# APC1_OBC.net
KiCad netlist of a schematic drawn in Altium Designer
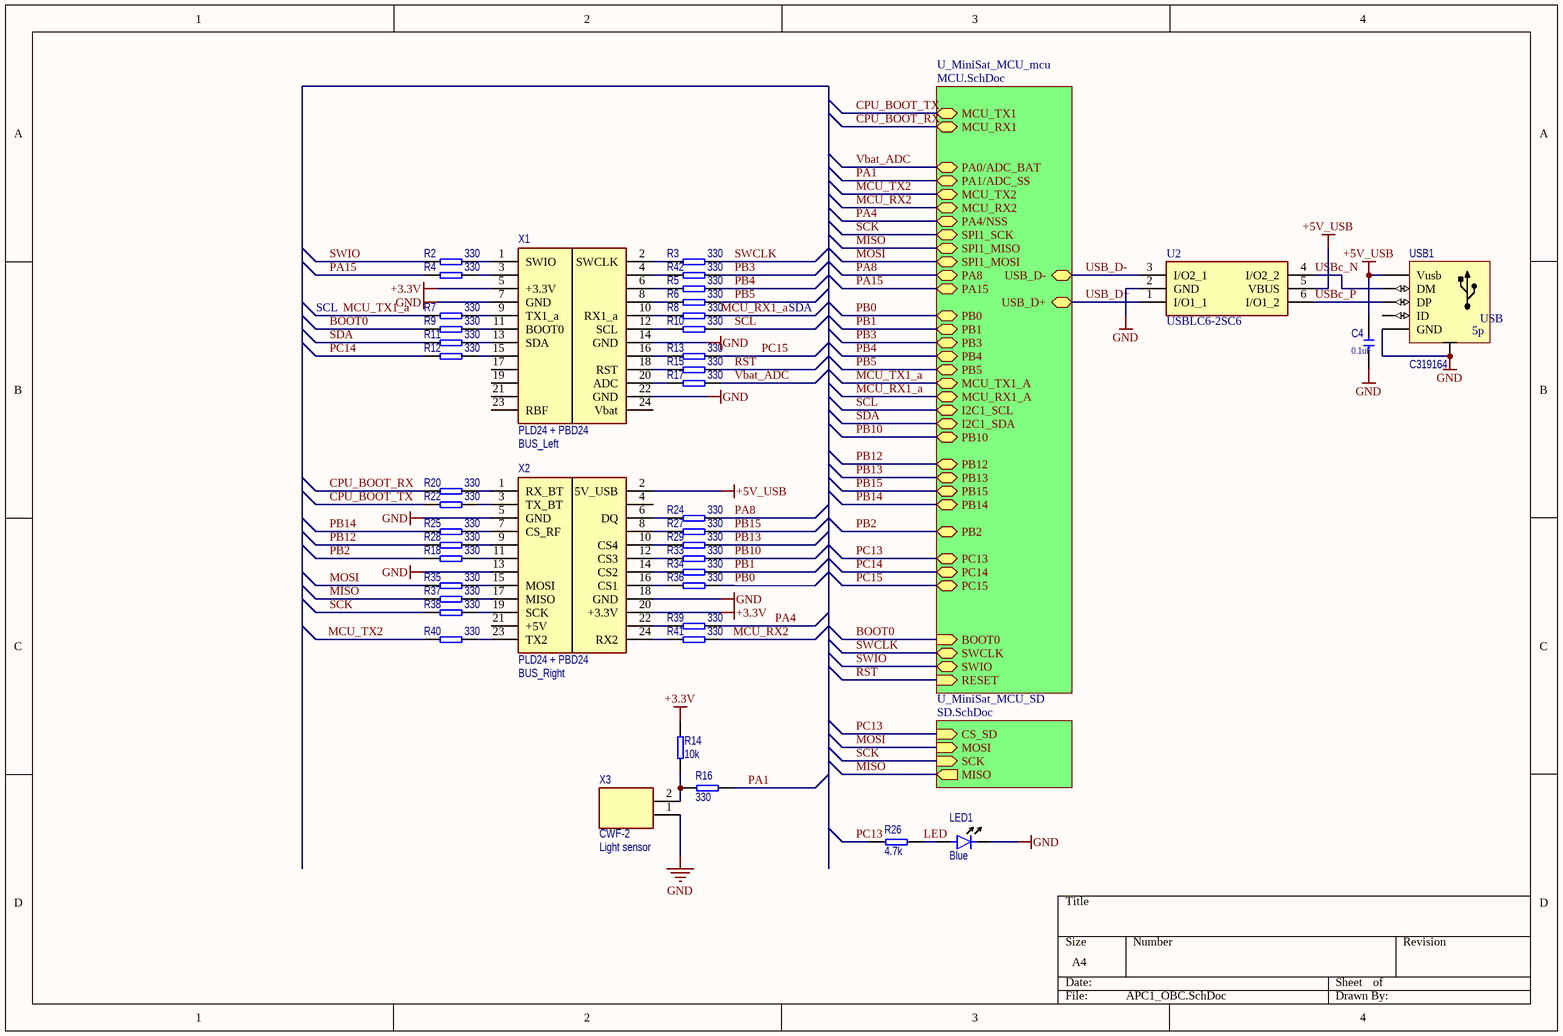
[diagram p0: APC1_OBC.SchDoc]

(export (version "E")
  (design (tool "Eeschema 10.0.6"))
  (components
    (comp (ref "C4")
      (value "0.1uF")
      (footprint "CERCAP 0402")
      (description "Capacitor")
      (fields (field (name "Comment") "CERCAP 0402 0.1uF * X7R"))
      (libsource (lib "!main") (part "!Capacitor"))
    )
    (comp (ref "LED1")
      (value "Blue")
      (footprint "LED 0603")
      (description "Light Emittering Diode")
      (fields (field (name "Comment") "LED 0603 Blue"))
      (libsource (lib "!main") (part "LED"))
    )
    (comp (ref "R2")
      (value "330")
      (footprint "RES 0402")
      (description "Resistor")
      (fields (field (name "Comment") "RES 0402 330"))
      (libsource (lib "!main") (part "!Resistor"))
    )
    (comp (ref "R3")
      (value "330")
      (footprint "RES 0402")
      (description "Resistor")
      (fields (field (name "Comment") "RES 0402 330"))
      (libsource (lib "!main") (part "!Resistor"))
    )
    (comp (ref "R4")
      (value "330")
      (footprint "RES 0402")
      (description "Resistor")
      (fields (field (name "Comment") "RES 0402 330"))
      (libsource (lib "!main") (part "!Resistor"))
    )
    (comp (ref "R5")
      (value "330")
      (footprint "RES 0402")
      (description "Resistor")
      (fields (field (name "Comment") "RES 0402 330"))
      (libsource (lib "!main") (part "!Resistor"))
    )
    (comp (ref "R6")
      (value "330")
      (footprint "RES 0402")
      (description "Resistor")
      (fields (field (name "Comment") "RES 0402 330"))
      (libsource (lib "!main") (part "!Resistor"))
    )
    (comp (ref "R7")
      (value "330")
      (footprint "RES 0402")
      (description "Resistor")
      (fields (field (name "Comment") "RES 0402 330"))
      (libsource (lib "!main") (part "!Resistor"))
    )
    (comp (ref "R8")
      (value "330")
      (footprint "RES 0402")
      (description "Resistor")
      (fields (field (name "Comment") "RES 0402 330"))
      (libsource (lib "!main") (part "!Resistor"))
    )
    (comp (ref "R9")
      (value "330")
      (footprint "RES 0402")
      (description "Resistor")
      (fields (field (name "Comment") "RES 0402 330"))
      (libsource (lib "!main") (part "!Resistor"))
    )
    (comp (ref "R10")
      (value "330")
      (footprint "RES 0402")
      (description "Resistor")
      (fields (field (name "Comment") "RES 0402 330"))
      (libsource (lib "!main") (part "!Resistor"))
    )
    (comp (ref "R11")
      (value "330")
      (footprint "RES 0402")
      (description "Resistor")
      (fields (field (name "Comment") "RES 0402 330"))
      (libsource (lib "!main") (part "!Resistor"))
    )
    (comp (ref "R12")
      (value "330")
      (footprint "RES 0402")
      (description "Resistor")
      (fields (field (name "Comment") "RES 0402 330"))
      (libsource (lib "!main") (part "!Resistor"))
    )
    (comp (ref "R13")
      (value "330")
      (footprint "RES 0402")
      (description "Resistor")
      (fields (field (name "Comment") "RES 0402 330"))
      (libsource (lib "!main") (part "!Resistor"))
    )
    (comp (ref "R14")
      (value "10k")
      (footprint "RES 0402")
      (description "Resistor")
      (fields (field (name "Comment") "RES 0402 10k"))
      (libsource (lib "!main") (part "!Resistor"))
    )
    (comp (ref "R15")
      (value "330")
      (footprint "RES 0402")
      (description "Resistor")
      (fields (field (name "Comment") "RES 0402 330"))
      (libsource (lib "!main") (part "!Resistor"))
    )
    (comp (ref "R16")
      (value "330")
      (footprint "RES 0603")
      (description "Resistor")
      (fields (field (name "Comment") "RES 0603 330"))
      (libsource (lib "!main") (part "!Resistor"))
    )
    (comp (ref "R17")
      (value "330")
      (footprint "RES 0402")
      (description "Resistor")
      (fields (field (name "Comment") "RES 0402 330"))
      (libsource (lib "!main") (part "!Resistor"))
    )
    (comp (ref "R18")
      (value "330")
      (footprint "RES 0402")
      (description "Resistor")
      (fields (field (name "Comment") "RES 0402 330"))
      (libsource (lib "!main") (part "!Resistor"))
    )
    (comp (ref "R20")
      (value "330")
      (footprint "RES 0402")
      (description "Resistor")
      (fields (field (name "Comment") "RES 0402 330"))
      (libsource (lib "!main") (part "!Resistor"))
    )
    (comp (ref "R22")
      (value "330")
      (footprint "RES 0402")
      (description "Resistor")
      (fields (field (name "Comment") "RES 0402 330"))
      (libsource (lib "!main") (part "!Resistor"))
    )
    (comp (ref "R24")
      (value "330")
      (footprint "RES 0402")
      (description "Resistor")
      (fields (field (name "Comment") "RES 0402 330"))
      (libsource (lib "!main") (part "!Resistor"))
    )
    (comp (ref "R25")
      (value "330")
      (footprint "RES 0402")
      (description "Resistor")
      (fields (field (name "Comment") "RES 0402 330"))
      (libsource (lib "!main") (part "!Resistor"))
    )
    (comp (ref "R26")
      (value "4.7k")
      (footprint "RES 0402")
      (description "Resistor")
      (fields (field (name "Comment") "RES 0402 4.7k"))
      (libsource (lib "!main") (part "!Resistor"))
    )
    (comp (ref "R27")
      (value "330")
      (footprint "RES 0402")
      (description "Resistor")
      (fields (field (name "Comment") "RES 0402 330"))
      (libsource (lib "!main") (part "!Resistor"))
    )
    (comp (ref "R28")
      (value "330")
      (footprint "RES 0402")
      (description "Resistor")
      (fields (field (name "Comment") "RES 0402 330"))
      (libsource (lib "!main") (part "!Resistor"))
    )
    (comp (ref "R29")
      (value "330")
      (footprint "RES 0402")
      (description "Resistor")
      (fields (field (name "Comment") "RES 0402 330"))
      (libsource (lib "!main") (part "!Resistor"))
    )
    (comp (ref "R33")
      (value "330")
      (footprint "RES 0402")
      (description "Resistor")
      (fields (field (name "Comment") "RES 0402 330"))
      (libsource (lib "!main") (part "!Resistor"))
    )
    (comp (ref "R34")
      (value "330")
      (footprint "RES 0402")
      (description "Resistor")
      (fields (field (name "Comment") "RES 0402 330"))
      (libsource (lib "!main") (part "!Resistor"))
    )
    (comp (ref "R35")
      (value "330")
      (footprint "RES 0402")
      (description "Resistor")
      (fields (field (name "Comment") "RES 0402 330"))
      (libsource (lib "!main") (part "!Resistor"))
    )
    (comp (ref "R36")
      (value "330")
      (footprint "RES 0402")
      (description "Resistor")
      (fields (field (name "Comment") "RES 0402 330"))
      (libsource (lib "!main") (part "!Resistor"))
    )
    (comp (ref "R37")
      (value "330")
      (footprint "RES 0402")
      (description "Resistor")
      (fields (field (name "Comment") "RES 0402 330"))
      (libsource (lib "!main") (part "!Resistor"))
    )
    (comp (ref "R38")
      (value "330")
      (footprint "RES 0402")
      (description "Resistor")
      (fields (field (name "Comment") "RES 0402 330"))
      (libsource (lib "!main") (part "!Resistor"))
    )
    (comp (ref "R39")
      (value "330")
      (footprint "RES 0402")
      (description "Resistor")
      (fields (field (name "Comment") "RES 0402 330"))
      (libsource (lib "!main") (part "!Resistor"))
    )
    (comp (ref "R40")
      (value "330")
      (footprint "RES 0402")
      (description "Resistor")
      (fields (field (name "Comment") "RES 0402 330"))
      (libsource (lib "!main") (part "!Resistor"))
    )
    (comp (ref "R41")
      (value "330")
      (footprint "RES 0402")
      (description "Resistor")
      (fields (field (name "Comment") "RES 0402 330"))
      (libsource (lib "!main") (part "!Resistor"))
    )
    (comp (ref "R42")
      (value "330")
      (footprint "RES 0402")
      (description "Resistor")
      (fields (field (name "Comment") "RES 0402 330"))
      (libsource (lib "!main") (part "!Resistor"))
    )
    (comp (ref "U2")
      (value "USBLC6-2SC6")
      (footprint "SOT-666")
      (description "Integrated Circuit")
      (fields (field (name "LCSC PART #") "C7519"))
      (libsource (lib "*") (part "USBLC6-2SC6"))
    )
    (comp (ref "USB1")
      (value "C319164")
      (footprint "USB-Micro_TH")
      (description "USB 5-pin")
      (libsource (lib "connectors") (part "USB(5p)"))
    )
    (comp (ref "X1")
      (value "PLD24 + PBD24")
      (footprint "PICOSAT_CNN")
      (description "10x2 header")
      (fields (field (name "PURPOSE") "BUS_Left"))
      (libsource (lib "connectors") (part "Header 2x12"))
    )
    (comp (ref "X2")
      (value "PLD24 + PBD24")
      (footprint "PICOSAT_CNN")
      (description "10x2 header")
      (fields (field (name "PURPOSE") "BUS_Right"))
      (libsource (lib "connectors") (part "Header 2x12"))
    )
    (comp (ref "X3")
      (value "CWF-2")
      (footprint "PBS-2-2.54")
      (description "2x1 header")
      (fields (field (name "PURPOSE") "Light sensor"))
      (libsource (lib "connectors") (part "Header 1x2"))
    )
  )
  (nets
    (net (code "1") (name "+3.3V") (class "Default")
      (node (ref "R14") (pin "2") (pinfunction "12_2") (pintype "passive"))
      (node (ref "X1") (pin "5") (pinfunction "+3.3V_5") (pintype "passive"))
      (node (ref "X2") (pin "20") (pinfunction "ADC_20") (pintype "passive"))
    )
    (net (code "2") (name "+5V_USB") (class "Default")
      (node (ref "C4") (pin "2") (pintype "passive"))
      (node (ref "U2") (pin "5") (pinfunction "VBUS_5") (pintype "passive"))
      (node (ref "USB1") (pin "Vusb") (pinfunction "Vusb_Vusb") (pintype "power_in"))
      (node (ref "X2") (pin "2") (pinfunction "SWCLK_2") (pintype "passive"))
    )
    (net (code "3") (name "/BOOT0") (class "Default")
      (node (ref "R9") (pin "1") (pinfunction "11_1") (pintype "passive"))
    )
    (net (code "4") (name "/CPU_BOOT_RX") (class "Default")
      (node (ref "R20") (pin "1") (pinfunction "11_1") (pintype "passive"))
    )
    (net (code "5") (name "/CPU_BOOT_TX") (class "Default")
      (node (ref "R22") (pin "1") (pinfunction "11_1") (pintype "passive"))
    )
    (net (code "6") (name "/LED") (class "Default")
      (node (ref "LED1") (pin "1") (pinfunction "Anode_1") (pintype "passive"))
      (node (ref "R26") (pin "2") (pinfunction "12_2") (pintype "passive"))
    )
    (net (code "7") (name "/MCU_RX1_a") (class "Default")
      (node (ref "R8") (pin "2") (pinfunction "12_2") (pintype "passive"))
    )
    (net (code "8") (name "/MCU_RX2") (class "Default")
      (node (ref "R41") (pin "2") (pinfunction "12_2") (pintype "passive"))
    )
    (net (code "9") (name "/MCU_TX1_a") (class "Default")
      (node (ref "R7") (pin "1") (pinfunction "11_1") (pintype "passive"))
    )
    (net (code "10") (name "/MCU_TX2") (class "Default")
      (node (ref "R40") (pin "1") (pinfunction "11_1") (pintype "passive"))
    )
    (net (code "11") (name "/MISO") (class "Default")
      (node (ref "R37") (pin "1") (pinfunction "11_1") (pintype "passive"))
    )
    (net (code "12") (name "/MOSI") (class "Default")
      (node (ref "R35") (pin "1") (pinfunction "11_1") (pintype "passive"))
    )
    (net (code "13") (name "/PA1") (class "Default")
      (node (ref "R16") (pin "1") (pinfunction "11_1") (pintype "passive"))
    )
    (net (code "14") (name "/PA4") (class "Default")
      (node (ref "R39") (pin "2") (pinfunction "12_2") (pintype "passive"))
    )
    (net (code "15") (name "/PA8") (class "Default")
      (node (ref "R24") (pin "2") (pinfunction "12_2") (pintype "passive"))
    )
    (net (code "16") (name "/PA15") (class "Default")
      (node (ref "R4") (pin "1") (pinfunction "11_1") (pintype "passive"))
    )
    (net (code "17") (name "/PB0") (class "Default")
      (node (ref "R36") (pin "2") (pinfunction "12_2") (pintype "passive"))
    )
    (net (code "18") (name "/PB1") (class "Default")
      (node (ref "R34") (pin "2") (pinfunction "12_2") (pintype "passive"))
    )
    (net (code "19") (name "/PB2") (class "Default")
      (node (ref "R18") (pin "1") (pinfunction "11_1") (pintype "passive"))
    )
    (net (code "20") (name "/PB3") (class "Default")
      (node (ref "R42") (pin "2") (pinfunction "12_2") (pintype "passive"))
    )
    (net (code "21") (name "/PB4") (class "Default")
      (node (ref "R5") (pin "2") (pinfunction "12_2") (pintype "passive"))
    )
    (net (code "22") (name "/PB5") (class "Default")
      (node (ref "R6") (pin "2") (pinfunction "12_2") (pintype "passive"))
    )
    (net (code "23") (name "/PB10") (class "Default")
      (node (ref "R33") (pin "2") (pinfunction "12_2") (pintype "passive"))
    )
    (net (code "24") (name "/PB12") (class "Default")
      (node (ref "R28") (pin "1") (pinfunction "11_1") (pintype "passive"))
    )
    (net (code "25") (name "/PB13") (class "Default")
      (node (ref "R29") (pin "2") (pinfunction "12_2") (pintype "passive"))
    )
    (net (code "26") (name "/PB14") (class "Default")
      (node (ref "R25") (pin "1") (pinfunction "11_1") (pintype "passive"))
    )
    (net (code "27") (name "/PB15") (class "Default")
      (node (ref "R27") (pin "2") (pinfunction "12_2") (pintype "passive"))
    )
    (net (code "28") (name "/PC13") (class "Default")
      (node (ref "R26") (pin "1") (pinfunction "11_1") (pintype "passive"))
    )
    (net (code "29") (name "/PC14") (class "Default")
      (node (ref "R12") (pin "1") (pinfunction "11_1") (pintype "passive"))
    )
    (net (code "30") (name "/PC15") (class "Default")
      (node (ref "R13") (pin "2") (pinfunction "12_2") (pintype "passive"))
    )
    (net (code "31") (name "/RST") (class "Default")
      (node (ref "R15") (pin "2") (pinfunction "12_2") (pintype "passive"))
    )
    (net (code "32") (name "/SCK") (class "Default")
      (node (ref "R38") (pin "1") (pinfunction "11_1") (pintype "passive"))
    )
    (net (code "33") (name "/SCL") (class "Default")
      (node (ref "R10") (pin "2") (pinfunction "12_2") (pintype "passive"))
    )
    (net (code "34") (name "/SDA") (class "Default")
      (node (ref "R11") (pin "1") (pinfunction "11_1") (pintype "passive"))
    )
    (net (code "35") (name "/SWCLK") (class "Default")
      (node (ref "R3") (pin "2") (pinfunction "12_2") (pintype "passive"))
    )
    (net (code "36") (name "/SWIO") (class "Default")
      (node (ref "R2") (pin "1") (pinfunction "11_1") (pintype "passive"))
    )
    (net (code "37") (name "/USB_D+") (class "Default")
      (node (ref "U2") (pin "1") (pinfunction "I/O1_1_1") (pintype "passive"))
    )
    (net (code "38") (name "/USB_D-") (class "Default")
      (node (ref "U2") (pin "3") (pinfunction "I/O2_1_3") (pintype "passive"))
    )
    (net (code "39") (name "/USBc_N") (class "Default")
      (node (ref "U2") (pin "4") (pinfunction "I/O2_2_4") (pintype "passive"))
      (node (ref "USB1") (pin "DM") (pinfunction "DM_DM") (pintype "bidirectional"))
    )
    (net (code "40") (name "/USBc_P") (class "Default")
      (node (ref "U2") (pin "6") (pinfunction "I/O1_2_6") (pintype "passive"))
      (node (ref "USB1") (pin "DP") (pinfunction "DP_DP") (pintype "bidirectional"))
    )
    (net (code "41") (name "/Vbat_ADC") (class "Default")
      (node (ref "R17") (pin "2") (pinfunction "12_2") (pintype "passive"))
    )
    (net (code "42") (name "GND") (class "Default")
      (node (ref "C4") (pin "1") (pintype "passive"))
      (node (ref "LED1") (pin "2") (pinfunction "Cathode_2") (pintype "passive"))
      (node (ref "U2") (pin "2") (pinfunction "GND_2") (pintype "passive"))
      (node (ref "USB1") (pin "GND") (pinfunction "GND_GND") (pintype "power_in"))
      (node (ref "USB1") (pin "TH") (pinfunction "TH_TH") (pintype "power_in"))
      (node (ref "X1") (pin "14") (pinfunction "GND_14") (pintype "passive"))
      (node (ref "X1") (pin "22") (pinfunction "GND_22") (pintype "passive"))
      (node (ref "X1") (pin "7") (pinfunction "GND_7") (pintype "passive"))
      (node (ref "X2") (pin "13") (pinfunction "SDA_13") (pintype "passive"))
      (node (ref "X2") (pin "18") (pinfunction "RST_18") (pintype "passive"))
      (node (ref "X2") (pin "5") (pinfunction "+3.3V_5") (pintype "passive"))
      (node (ref "X3") (pin "1") (pinfunction "1_1") (pintype "passive"))
    )
    (net (code "43") (name "Net-(R2-12)") (class "Default")
      (node (ref "R2") (pin "2") (pinfunction "12_2") (pintype "passive"))
      (node (ref "X1") (pin "1") (pinfunction "SWIO_1") (pintype "passive"))
    )
    (net (code "44") (name "Net-(R3-11)") (class "Default")
      (node (ref "R3") (pin "1") (pinfunction "11_1") (pintype "passive"))
      (node (ref "X1") (pin "2") (pinfunction "SWCLK_2") (pintype "passive"))
    )
    (net (code "45") (name "Net-(R4-12)") (class "Default")
      (node (ref "R4") (pin "2") (pinfunction "12_2") (pintype "passive"))
      (node (ref "X1") (pin "3") (pintype "passive"))
    )
    (net (code "46") (name "Net-(R5-11)") (class "Default")
      (node (ref "R5") (pin "1") (pinfunction "11_1") (pintype "passive"))
      (node (ref "X1") (pin "6") (pintype "passive"))
    )
    (net (code "47") (name "Net-(R6-11)") (class "Default")
      (node (ref "R6") (pin "1") (pinfunction "11_1") (pintype "passive"))
      (node (ref "X1") (pin "8") (pintype "passive"))
    )
    (net (code "48") (name "Net-(R7-12)") (class "Default")
      (node (ref "R7") (pin "2") (pinfunction "12_2") (pintype "passive"))
      (node (ref "X1") (pin "9") (pinfunction "TX1_a_9") (pintype "passive"))
    )
    (net (code "49") (name "Net-(R8-11)") (class "Default")
      (node (ref "R8") (pin "1") (pinfunction "11_1") (pintype "passive"))
      (node (ref "X1") (pin "10") (pinfunction "RX1_a_10") (pintype "passive"))
    )
    (net (code "50") (name "Net-(R9-12)") (class "Default")
      (node (ref "R9") (pin "2") (pinfunction "12_2") (pintype "passive"))
      (node (ref "X1") (pin "11") (pinfunction "BOOT0_11") (pintype "passive"))
    )
    (net (code "51") (name "Net-(R10-11)") (class "Default")
      (node (ref "R10") (pin "1") (pinfunction "11_1") (pintype "passive"))
      (node (ref "X1") (pin "12") (pinfunction "SCL_12") (pintype "passive"))
    )
    (net (code "52") (name "Net-(R11-12)") (class "Default")
      (node (ref "R11") (pin "2") (pinfunction "12_2") (pintype "passive"))
      (node (ref "X1") (pin "13") (pinfunction "SDA_13") (pintype "passive"))
    )
    (net (code "53") (name "Net-(R12-12)") (class "Default")
      (node (ref "R12") (pin "2") (pinfunction "12_2") (pintype "passive"))
      (node (ref "X1") (pin "15") (pintype "passive"))
    )
    (net (code "54") (name "Net-(R13-11)") (class "Default")
      (node (ref "R13") (pin "1") (pinfunction "11_1") (pintype "passive"))
      (node (ref "X1") (pin "16") (pintype "passive"))
    )
    (net (code "55") (name "Net-(R14-11)") (class "Default")
      (node (ref "R14") (pin "1") (pinfunction "11_1") (pintype "passive"))
      (node (ref "R16") (pin "2") (pinfunction "12_2") (pintype "passive"))
      (node (ref "X3") (pin "2") (pinfunction "2_2") (pintype "passive"))
    )
    (net (code "56") (name "Net-(R15-11)") (class "Default")
      (node (ref "R15") (pin "1") (pinfunction "11_1") (pintype "passive"))
      (node (ref "X1") (pin "18") (pinfunction "RST_18") (pintype "passive"))
    )
    (net (code "57") (name "Net-(R17-11)") (class "Default")
      (node (ref "R17") (pin "1") (pinfunction "11_1") (pintype "passive"))
      (node (ref "X1") (pin "20") (pinfunction "ADC_20") (pintype "passive"))
    )
    (net (code "58") (name "Net-(R18-12)") (class "Default")
      (node (ref "R18") (pin "2") (pinfunction "12_2") (pintype "passive"))
      (node (ref "X2") (pin "11") (pinfunction "BOOT0_11") (pintype "passive"))
    )
    (net (code "59") (name "Net-(R20-12)") (class "Default")
      (node (ref "R20") (pin "2") (pinfunction "12_2") (pintype "passive"))
      (node (ref "X2") (pin "1") (pinfunction "SWIO_1") (pintype "passive"))
    )
    (net (code "60") (name "Net-(R22-12)") (class "Default")
      (node (ref "R22") (pin "2") (pinfunction "12_2") (pintype "passive"))
      (node (ref "X2") (pin "3") (pintype "passive"))
    )
    (net (code "61") (name "Net-(R24-11)") (class "Default")
      (node (ref "R24") (pin "1") (pinfunction "11_1") (pintype "passive"))
      (node (ref "X2") (pin "6") (pintype "passive"))
    )
    (net (code "62") (name "Net-(R25-12)") (class "Default")
      (node (ref "R25") (pin "2") (pinfunction "12_2") (pintype "passive"))
      (node (ref "X2") (pin "7") (pinfunction "GND_7") (pintype "passive"))
    )
    (net (code "63") (name "Net-(R27-11)") (class "Default")
      (node (ref "R27") (pin "1") (pinfunction "11_1") (pintype "passive"))
      (node (ref "X2") (pin "8") (pintype "passive"))
    )
    (net (code "64") (name "Net-(R28-12)") (class "Default")
      (node (ref "R28") (pin "2") (pinfunction "12_2") (pintype "passive"))
      (node (ref "X2") (pin "9") (pinfunction "TX1_a_9") (pintype "passive"))
    )
    (net (code "65") (name "Net-(R29-11)") (class "Default")
      (node (ref "R29") (pin "1") (pinfunction "11_1") (pintype "passive"))
      (node (ref "X2") (pin "10") (pinfunction "RX1_a_10") (pintype "passive"))
    )
    (net (code "66") (name "Net-(R33-11)") (class "Default")
      (node (ref "R33") (pin "1") (pinfunction "11_1") (pintype "passive"))
      (node (ref "X2") (pin "12") (pinfunction "SCL_12") (pintype "passive"))
    )
    (net (code "67") (name "Net-(R34-11)") (class "Default")
      (node (ref "R34") (pin "1") (pinfunction "11_1") (pintype "passive"))
      (node (ref "X2") (pin "14") (pinfunction "GND_14") (pintype "passive"))
    )
    (net (code "68") (name "Net-(R35-12)") (class "Default")
      (node (ref "R35") (pin "2") (pinfunction "12_2") (pintype "passive"))
      (node (ref "X2") (pin "15") (pintype "passive"))
    )
    (net (code "69") (name "Net-(R36-11)") (class "Default")
      (node (ref "R36") (pin "1") (pinfunction "11_1") (pintype "passive"))
      (node (ref "X2") (pin "16") (pintype "passive"))
    )
    (net (code "70") (name "Net-(R37-12)") (class "Default")
      (node (ref "R37") (pin "2") (pinfunction "12_2") (pintype "passive"))
      (node (ref "X2") (pin "17") (pintype "passive"))
    )
    (net (code "71") (name "Net-(R38-12)") (class "Default")
      (node (ref "R38") (pin "2") (pinfunction "12_2") (pintype "passive"))
      (node (ref "X2") (pin "19") (pintype "passive"))
    )
    (net (code "72") (name "Net-(R39-11)") (class "Default")
      (node (ref "R39") (pin "1") (pinfunction "11_1") (pintype "passive"))
      (node (ref "X2") (pin "22") (pinfunction "GND_22") (pintype "passive"))
    )
    (net (code "73") (name "Net-(R40-12)") (class "Default")
      (node (ref "R40") (pin "2") (pinfunction "12_2") (pintype "passive"))
      (node (ref "X2") (pin "23") (pinfunction "RBF_23") (pintype "passive"))
    )
    (net (code "74") (name "Net-(R41-11)") (class "Default")
      (node (ref "R41") (pin "1") (pinfunction "11_1") (pintype "passive"))
      (node (ref "X2") (pin "24") (pinfunction "Vbat_24") (pintype "passive"))
    )
    (net (code "75") (name "Net-(R42-11)") (class "Default")
      (node (ref "R42") (pin "1") (pinfunction "11_1") (pintype "passive"))
      (node (ref "X1") (pin "4") (pintype "passive"))
    )
    (net (code "76") (name "unconnected-(USB1-PadID)") (class "Default")
      (node (ref "USB1") (pin "ID") (pinfunction "ID_ID") (pintype "bidirectional"))
    )
    (net (code "77") (name "unconnected-(X1-Pad17)") (class "Default")
      (node (ref "X1") (pin "17") (pintype "passive"))
    )
    (net (code "78") (name "unconnected-(X1-Pad19)") (class "Default")
      (node (ref "X1") (pin "19") (pintype "passive"))
    )
    (net (code "79") (name "unconnected-(X1-Pad21)") (class "Default")
      (node (ref "X1") (pin "21") (pintype "passive"))
    )
    (net (code "80") (name "unconnected-(X1-RBF-Pad23)") (class "Default")
      (node (ref "X1") (pin "23") (pinfunction "RBF_23") (pintype "passive"))
    )
    (net (code "81") (name "unconnected-(X1-Vbat-Pad24)") (class "Default")
      (node (ref "X1") (pin "24") (pinfunction "Vbat_24") (pintype "passive"))
    )
    (net (code "82") (name "unconnected-(X2-Pad4)") (class "Default")
      (node (ref "X2") (pin "4") (pintype "passive"))
    )
    (net (code "83") (name "unconnected-(X2-Pad21)") (class "Default")
      (node (ref "X2") (pin "21") (pintype "passive"))
    )
  )
)
